# Schematic_v1_1.net
KiCad netlist of a schematic drawn in EasyEDA
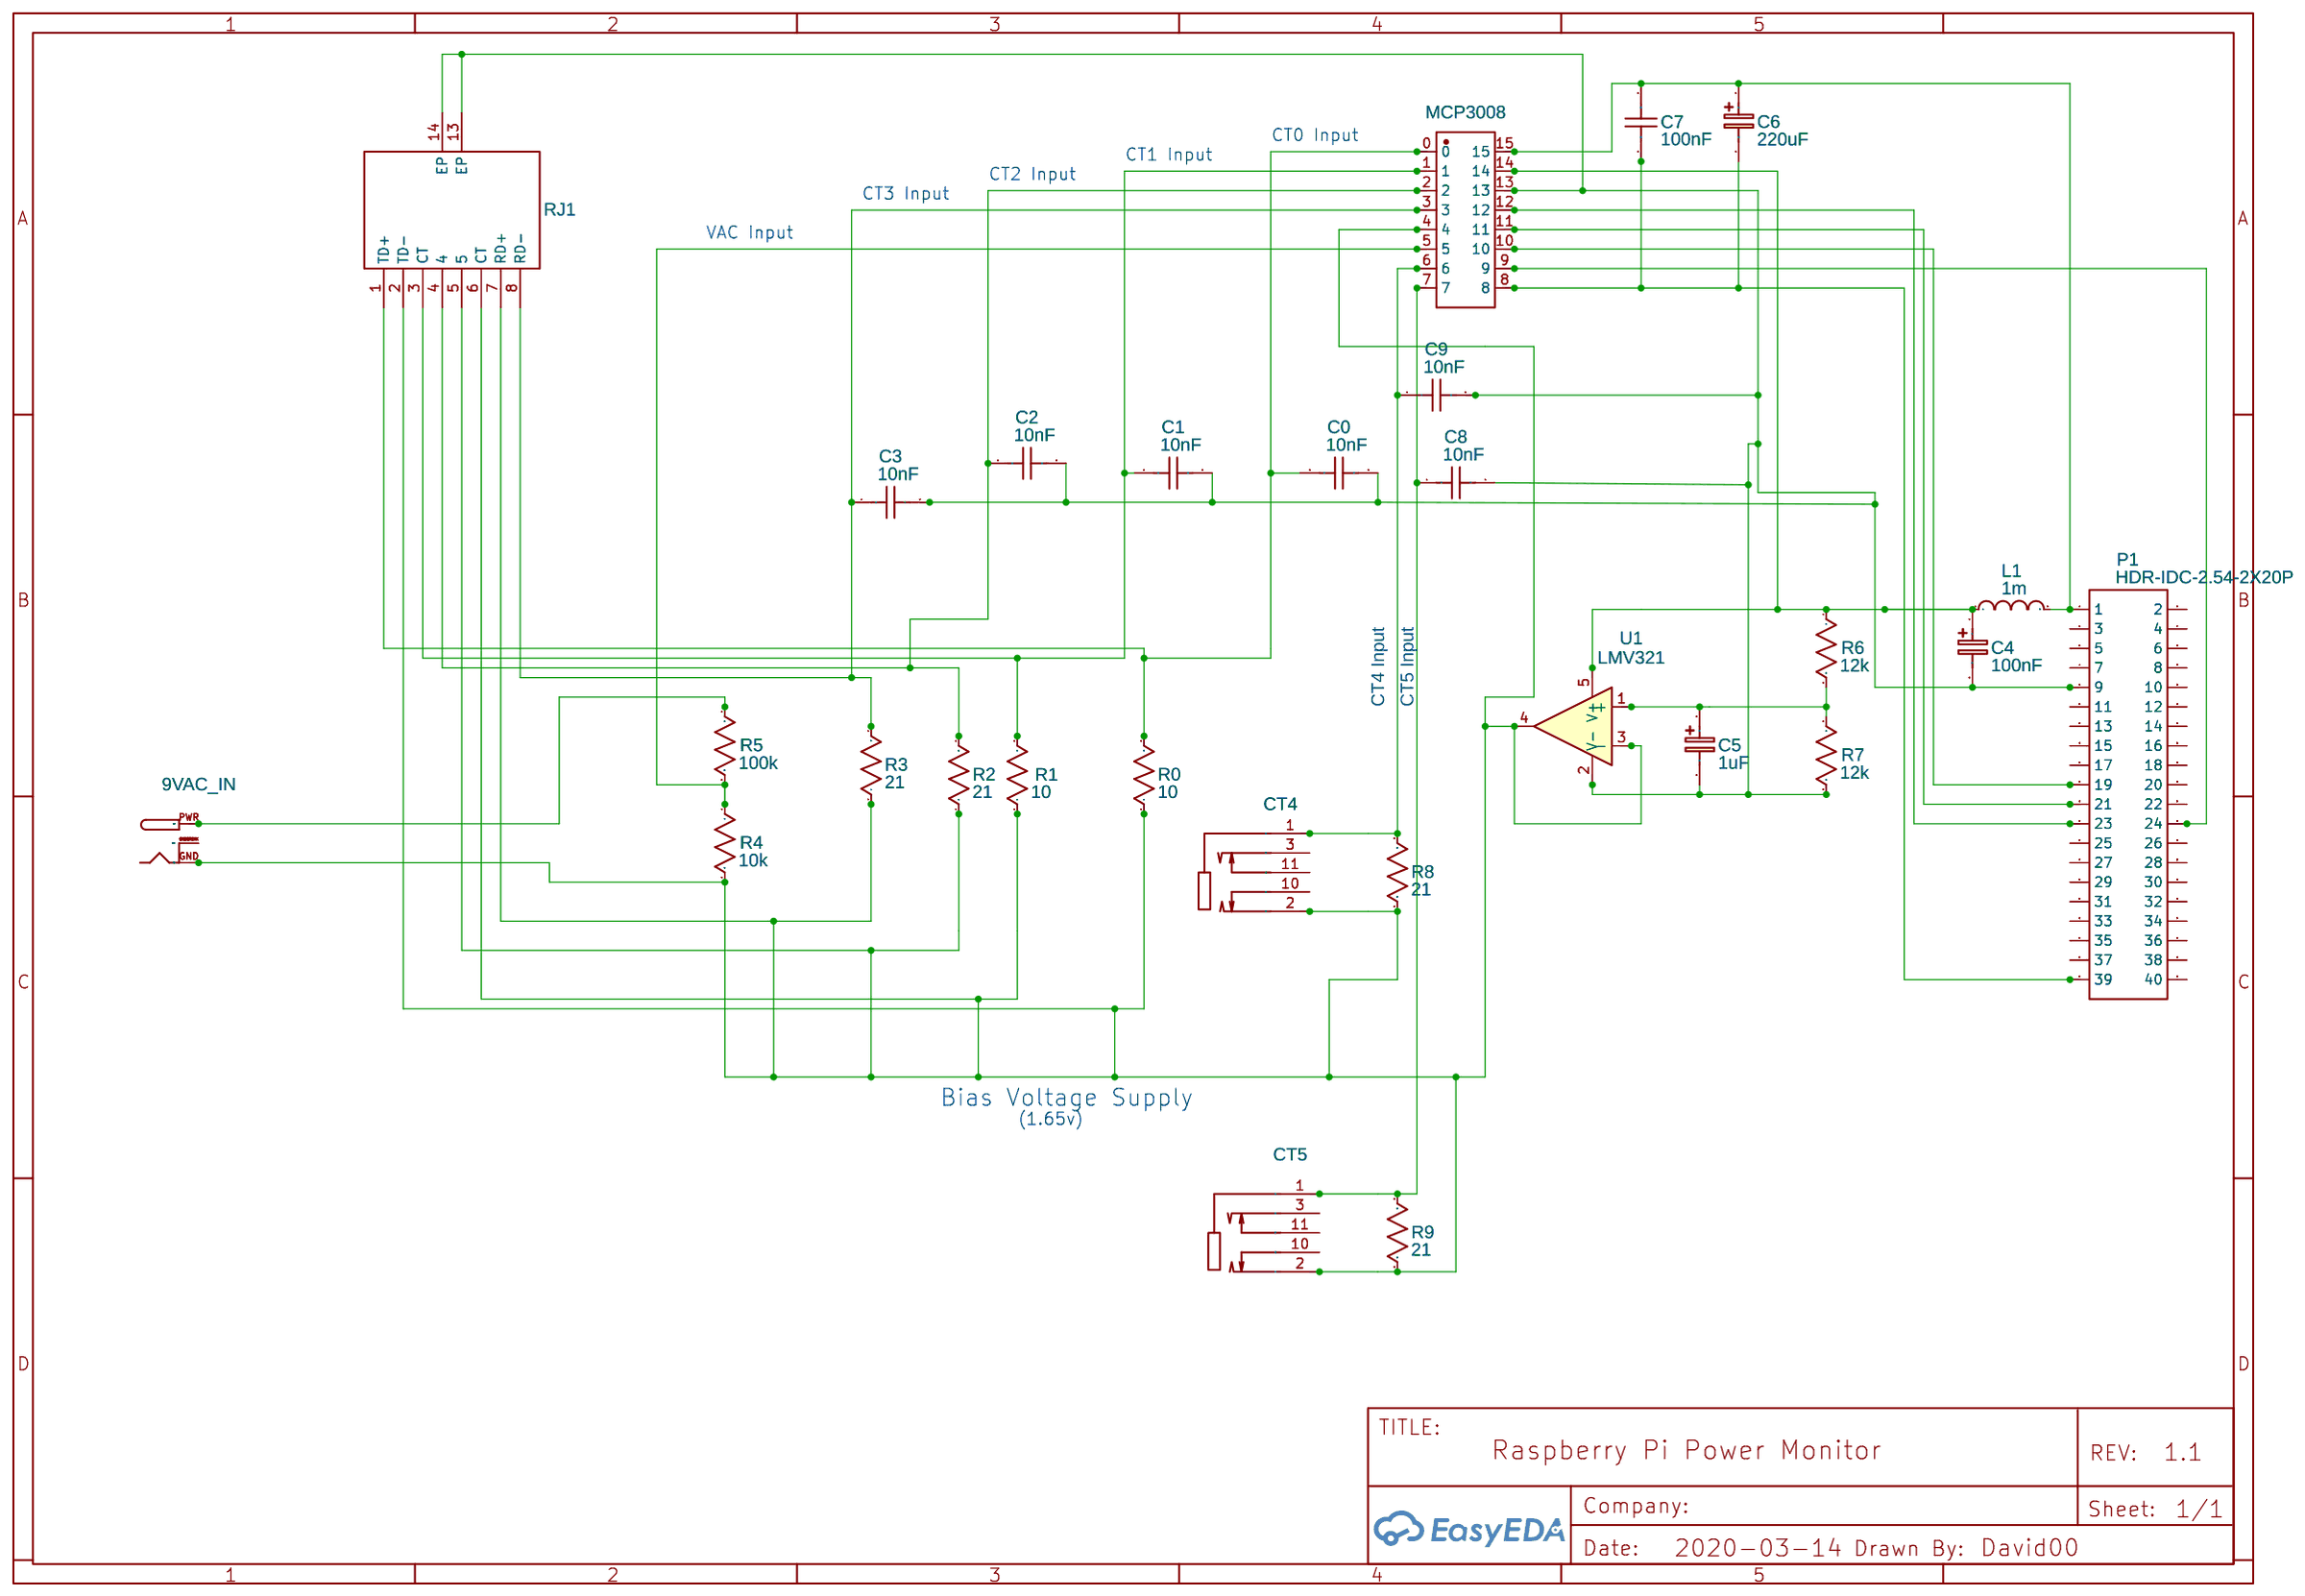
[diagram p0: schematic sheet]

(export (version "E")
  (design (tool "Eeschema 10.0.6"))
  (components
    (comp (ref "9VAC_IN") (value "DCBARRELPTH") (libsource (lib "") (part "DCBARRELPTH")))
    (comp (ref "C0")
      (value "10nF")
      (fields
        (field (name "BOM_Manufacturer Part") "PE103J2A0501")
        (field (name "BOM_Supplier Part") "C390168")
      )
      (libsource (lib "") (part "PE103J2A0501"))
    )
    (comp (ref "C1")
      (value "10nF")
      (fields
        (field (name "BOM_Manufacturer Part") "PE103J2A0501")
        (field (name "BOM_Supplier Part") "C390168")
      )
      (libsource (lib "") (part "PE103J2A0501"))
    )
    (comp (ref "C2")
      (value "10nF")
      (fields
        (field (name "BOM_Manufacturer Part") "PE103J2A0501")
        (field (name "BOM_Supplier Part") "C390168")
      )
      (libsource (lib "") (part "PE103J2A0501"))
    )
    (comp (ref "C3")
      (value "10nF")
      (fields
        (field (name "BOM_Manufacturer Part") "PE103J2A0501")
        (field (name "BOM_Supplier Part") "C390168")
      )
      (libsource (lib "") (part "PE103J2A0501"))
    )
    (comp (ref "C4") (value "100nF") (libsource (lib "") (part "Cap_Electrolytic(TH)_D3.0XF1.5_EU")))
    (comp (ref "C5") (value "1uF") (libsource (lib "") (part "Cap_Electrolytic(TH)_D3.0XF1.5_EU")))
    (comp (ref "C6") (value "220uF") (libsource (lib "") (part "Cap_Electrolytic(TH)_D3.0XF1.5_EU_1")))
    (comp (ref "C7")
      (value "100nF")
      (fields
        (field (name "BOM_Manufacturer Part") "CC45SL3AD101JYVNA")
        (field (name "BOM_Supplier Part") "C342396")
      )
      (libsource (lib "") (part "CC45SL3AD101JYVNA"))
    )
    (comp (ref "C8")
      (value "10nF")
      (fields
        (field (name "BOM_Manufacturer Part") "PE103J2A0501")
        (field (name "BOM_Supplier Part") "C390168")
      )
      (libsource (lib "") (part "PE103J2A0501"))
    )
    (comp (ref "C9")
      (value "10nF")
      (fields
        (field (name "BOM_Manufacturer Part") "PE103J2A0501")
        (field (name "BOM_Supplier Part") "C390168")
      )
      (libsource (lib "") (part "PE103J2A0501"))
    )
    (comp (ref "CT4")
      (value "PJ-328A0-B")
      (fields (field (name "BOM_Supplier Part") "C381129"))
      (libsource (lib "") (part "PJ-328A0-B"))
    )
    (comp (ref "CT5")
      (value "PJ-328A0-B")
      (fields (field (name "BOM_Supplier Part") "C381129"))
      (libsource (lib "") (part "PJ-328A0-B"))
    )
    (comp (ref "L1") (value "1m") (libsource (lib "") (part "Inductor_AXIAL-0.4_US")))
    (comp (ref "MCP3008")
      (value "IC seat 16P")
      (fields (field (name "BOM_Supplier Part") "C2326"))
      (libsource (lib "") (part "IC seat 16P"))
    )
    (comp (ref "P1")
      (value "HDR-IDC-2.54-2X20P")
      (fields
        (field (name "BOM_Manufacturer Part") "IDC Box 2X20 2.54MM")
        (field (name "BOM_Supplier Part") "C9138")
      )
      (libsource (lib "") (part "HDR-IDC-2.54-2X20P"))
    )
    (comp (ref "R0") (value "10") (libsource (lib "") (part "Res_AXIAL-0.3(1/8W)_US")))
    (comp (ref "R1") (value "10") (libsource (lib "") (part "Res_AXIAL-0.3(1/8W)_US")))
    (comp (ref "R2") (value "21") (libsource (lib "") (part "Res_AXIAL-0.3(1/8W)_US")))
    (comp (ref "R3") (value "21") (libsource (lib "") (part "Res_AXIAL-0.3(1/8W)_US")))
    (comp (ref "R4") (value "10k") (libsource (lib "") (part "Res_AXIAL-0.3(1/8W)_US_1")))
    (comp (ref "R5") (value "100k") (libsource (lib "") (part "Res_AXIAL-0.3(1/8W)_US_1")))
    (comp (ref "R6") (value "12k") (libsource (lib "") (part "Res_AXIAL-0.3(1/8W)_US_1")))
    (comp (ref "R7") (value "12k") (libsource (lib "") (part "Res_AXIAL-0.3(1/8W)_US_1")))
    (comp (ref "R8") (value "21") (libsource (lib "") (part "Res_AXIAL-0.3(1/8W)_US")))
    (comp (ref "R9") (value "21") (libsource (lib "") (part "Res_AXIAL-0.3(1/8W)_US")))
    (comp (ref "RJ1")
      (value "13F-62ANWA2NL")
      (fields (field (name "BOM_Supplier Part") "C179761"))
      (libsource (lib "") (part "13F-62ANWA2NL"))
    )
    (comp (ref "U1") (value "LMV321") (libsource (lib "") (part "LMV321")))
  )
  (nets
    (net (code "1") (name "Net-(9VAC_IN-PadPWR)") (class "Default")
      (node (ref "9VAC_IN") (pin "PWR") (pinfunction "PWR_PWR") (pintype "passive"))
      (node (ref "R5") (pin "1") (pinfunction "1_1") (pintype "unspecified"))
    )
    (net (code "2") (name "Net-(C1-Pad1)") (class "Default")
      (node (ref "C1") (pin "1") (pinfunction "1_1") (pintype "unspecified"))
      (node (ref "MCP3008") (pin "1") (pinfunction "1_1") (pintype "unspecified"))
      (node (ref "R1") (pin "2") (pinfunction "2_2") (pintype "unspecified"))
      (node (ref "RJ1") (pin "3") (pinfunction "CT_3") (pintype "unspecified"))
    )
    (net (code "3") (name "Net-(C2-Pad1)") (class "Default")
      (node (ref "C2") (pin "1") (pinfunction "1_1") (pintype "unspecified"))
      (node (ref "MCP3008") (pin "2") (pinfunction "2_2") (pintype "unspecified"))
      (node (ref "R2") (pin "2") (pinfunction "2_2") (pintype "unspecified"))
      (node (ref "RJ1") (pin "4") (pinfunction "4_4") (pintype "unspecified"))
    )
    (net (code "4") (name "Net-(C6-Pad1)") (class "Default")
      (node (ref "C6") (pin "1") (pinfunction "1_1") (pintype "unspecified"))
      (node (ref "C7") (pin "2") (pinfunction "2_2") (pintype "unspecified"))
      (node (ref "L1") (pin "2") (pinfunction "2_2") (pintype "unspecified"))
      (node (ref "MCP3008") (pin "15") (pinfunction "15_15") (pintype "unspecified"))
      (node (ref "P1") (pin "1") (pinfunction "1_1") (pintype "unspecified"))
    )
    (net (code "5") (name "Net-(C6-Pad2)") (class "Default")
      (node (ref "C6") (pin "2") (pinfunction "2_2") (pintype "unspecified"))
      (node (ref "C7") (pin "1") (pinfunction "1_1") (pintype "unspecified"))
      (node (ref "MCP3008") (pin "8") (pinfunction "8_8") (pintype "unspecified"))
      (node (ref "P1") (pin "39") (pinfunction "39_39") (pintype "unspecified"))
    )
    (net (code "6") (name "Net-(C8-Pad1)") (class "Default")
      (node (ref "C8") (pin "1") (pinfunction "1_1") (pintype "unspecified"))
      (node (ref "CT5") (pin "1") (pinfunction "1_1") (pintype "unspecified"))
      (node (ref "MCP3008") (pin "7") (pinfunction "7_7") (pintype "unspecified"))
      (node (ref "R9") (pin "2") (pinfunction "2_2") (pintype "unspecified"))
    )
    (net (code "7") (name "Net-(C9-Pad1)") (class "Default")
      (node (ref "C9") (pin "1") (pinfunction "1_1") (pintype "unspecified"))
      (node (ref "CT4") (pin "1") (pinfunction "1_1") (pintype "unspecified"))
      (node (ref "MCP3008") (pin "6") (pinfunction "6_6") (pintype "unspecified"))
      (node (ref "R8") (pin "2") (pinfunction "2_2") (pintype "unspecified"))
    )
    (net (code "8") (name "Net-(MCP3008-Pad5)") (class "Default")
      (node (ref "MCP3008") (pin "5") (pinfunction "5_5") (pintype "unspecified"))
      (node (ref "R4") (pin "1") (pinfunction "1_1") (pintype "unspecified"))
      (node (ref "R5") (pin "2") (pinfunction "2_2") (pintype "unspecified"))
    )
    (net (code "9") (name "Net-(MCP3008-Pad9)") (class "Default")
      (node (ref "MCP3008") (pin "9") (pinfunction "9_9") (pintype "unspecified"))
      (node (ref "P1") (pin "24") (pinfunction "24_24") (pintype "unspecified"))
    )
    (net (code "10") (name "Net-(MCP3008-Pad10)") (class "Default")
      (node (ref "MCP3008") (pin "10") (pinfunction "10_10") (pintype "unspecified"))
      (node (ref "P1") (pin "19") (pinfunction "19_19") (pintype "unspecified"))
    )
    (net (code "11") (name "Net-(MCP3008-Pad11)") (class "Default")
      (node (ref "MCP3008") (pin "11") (pinfunction "11_11") (pintype "unspecified"))
      (node (ref "P1") (pin "21") (pinfunction "21_21") (pintype "unspecified"))
    )
    (net (code "12") (name "Net-(MCP3008-Pad12)") (class "Default")
      (node (ref "MCP3008") (pin "12") (pinfunction "12_12") (pintype "unspecified"))
      (node (ref "P1") (pin "23") (pinfunction "23_23") (pintype "unspecified"))
    )
    (net (code "13") (name "Net-(RJ1-RD+)") (class "Default")
      (node (ref "9VAC_IN") (pin "GND") (pinfunction "GND_GND") (pintype "passive"))
      (node (ref "CT4") (pin "2") (pinfunction "2_2") (pintype "unspecified"))
      (node (ref "CT5") (pin "2") (pinfunction "2_2") (pintype "unspecified"))
      (node (ref "MCP3008") (pin "4") (pinfunction "4_4") (pintype "unspecified"))
      (node (ref "R0") (pin "1") (pinfunction "1_1") (pintype "unspecified"))
      (node (ref "R1") (pin "1") (pinfunction "1_1") (pintype "unspecified"))
      (node (ref "R2") (pin "1") (pinfunction "1_1") (pintype "unspecified"))
      (node (ref "R3") (pin "1") (pinfunction "1_1") (pintype "unspecified"))
      (node (ref "R4") (pin "2") (pinfunction "2_2") (pintype "unspecified"))
      (node (ref "R8") (pin "1") (pinfunction "1_1") (pintype "unspecified"))
      (node (ref "R9") (pin "1") (pinfunction "1_1") (pintype "unspecified"))
      (node (ref "RJ1") (pin "2") (pinfunction "TD-_2") (pintype "unspecified"))
      (node (ref "RJ1") (pin "5") (pinfunction "5_5") (pintype "unspecified"))
      (node (ref "RJ1") (pin "6") (pinfunction "CT_6") (pintype "unspecified"))
      (node (ref "RJ1") (pin "7") (pinfunction "RD+_7") (pintype "unspecified"))
      (node (ref "U1") (pin "3") (pinfunction "-_3") (pintype "input"))
      (node (ref "U1") (pin "4") (pintype "output"))
    )
    (net (code "14") (name "Net-(RJ1-RD-)") (class "Default")
      (node (ref "C3") (pin "1") (pinfunction "1_1") (pintype "unspecified"))
      (node (ref "MCP3008") (pin "3") (pinfunction "3_3") (pintype "unspecified"))
      (node (ref "R3") (pin "2") (pinfunction "2_2") (pintype "unspecified"))
      (node (ref "RJ1") (pin "8") (pinfunction "RD-_8") (pintype "unspecified"))
    )
    (net (code "15") (name "Net-(RJ1-TD+)") (class "Default")
      (node (ref "C0") (pin "1") (pinfunction "1_1") (pintype "unspecified"))
      (node (ref "MCP3008") (pin "0") (pinfunction "0_0") (pintype "unspecified"))
      (node (ref "R0") (pin "2") (pinfunction "2_2") (pintype "unspecified"))
      (node (ref "RJ1") (pin "1") (pinfunction "TD+_1") (pintype "unspecified"))
    )
    (net (code "16") (name "Net-(U1-+)") (class "Default")
      (node (ref "C5") (pin "1") (pinfunction "1_1") (pintype "unspecified"))
      (node (ref "R6") (pin "2") (pinfunction "2_2") (pintype "unspecified"))
      (node (ref "R7") (pin "1") (pinfunction "1_1") (pintype "unspecified"))
      (node (ref "U1") (pin "1") (pinfunction "+_1") (pintype "input"))
    )
    (net (code "17") (name "Net-(U1-V+)") (class "Default")
      (node (ref "C4") (pin "1") (pinfunction "1_1") (pintype "unspecified"))
      (node (ref "L1") (pin "1") (pinfunction "1_1") (pintype "unspecified"))
      (node (ref "MCP3008") (pin "14") (pinfunction "14_14") (pintype "unspecified"))
      (node (ref "R6") (pin "1") (pinfunction "1_1") (pintype "unspecified"))
      (node (ref "U1") (pin "5") (pinfunction "V+_5") (pintype "bidirectional"))
    )
    (net (code "18") (name "Net-(U1-V-)") (class "Default")
      (node (ref "C0") (pin "2") (pinfunction "2_2") (pintype "unspecified"))
      (node (ref "C1") (pin "2") (pinfunction "2_2") (pintype "unspecified"))
      (node (ref "C2") (pin "2") (pinfunction "2_2") (pintype "unspecified"))
      (node (ref "C3") (pin "2") (pinfunction "2_2") (pintype "unspecified"))
      (node (ref "C4") (pin "2") (pinfunction "2_2") (pintype "unspecified"))
      (node (ref "C5") (pin "2") (pinfunction "2_2") (pintype "unspecified"))
      (node (ref "C8") (pin "2") (pinfunction "2_2") (pintype "unspecified"))
      (node (ref "C9") (pin "2") (pinfunction "2_2") (pintype "unspecified"))
      (node (ref "MCP3008") (pin "13") (pinfunction "13_13") (pintype "unspecified"))
      (node (ref "P1") (pin "9") (pinfunction "9_9") (pintype "unspecified"))
      (node (ref "R7") (pin "2") (pinfunction "2_2") (pintype "unspecified"))
      (node (ref "RJ1") (pin "13") (pinfunction "EP_13") (pintype "unspecified"))
      (node (ref "RJ1") (pin "14") (pinfunction "EP_14") (pintype "unspecified"))
      (node (ref "U1") (pin "2") (pinfunction "V-_2") (pintype "bidirectional"))
    )
    (net (code "19") (name "unconnected-(9VAC_IN-PadGNDBREAK)") (class "Default")
      (node (ref "9VAC_IN") (pin "GNDBREAK") (pinfunction "GNDBREAK_GNDBREAK") (pintype "passive"))
    )
    (net (code "20") (name "unconnected-(CT4-Pad3)") (class "Default")
      (node (ref "CT4") (pin "3") (pinfunction "3_3") (pintype "unspecified"))
    )
    (net (code "21") (name "unconnected-(CT4-Pad10)") (class "Default")
      (node (ref "CT4") (pin "10") (pinfunction "10_10") (pintype "unspecified"))
    )
    (net (code "22") (name "unconnected-(CT4-Pad11)") (class "Default")
      (node (ref "CT4") (pin "11") (pinfunction "11_11") (pintype "unspecified"))
    )
    (net (code "23") (name "unconnected-(CT5-Pad3)") (class "Default")
      (node (ref "CT5") (pin "3") (pinfunction "3_3") (pintype "unspecified"))
    )
    (net (code "24") (name "unconnected-(CT5-Pad10)") (class "Default")
      (node (ref "CT5") (pin "10") (pinfunction "10_10") (pintype "unspecified"))
    )
    (net (code "25") (name "unconnected-(CT5-Pad11)") (class "Default")
      (node (ref "CT5") (pin "11") (pinfunction "11_11") (pintype "unspecified"))
    )
    (net (code "26") (name "unconnected-(P1-Pad2)") (class "Default")
      (node (ref "P1") (pin "2") (pinfunction "2_2") (pintype "unspecified"))
    )
    (net (code "27") (name "unconnected-(P1-Pad3)") (class "Default")
      (node (ref "P1") (pin "3") (pinfunction "3_3") (pintype "unspecified"))
    )
    (net (code "28") (name "unconnected-(P1-Pad4)") (class "Default")
      (node (ref "P1") (pin "4") (pinfunction "4_4") (pintype "unspecified"))
    )
    (net (code "29") (name "unconnected-(P1-Pad5)") (class "Default")
      (node (ref "P1") (pin "5") (pinfunction "5_5") (pintype "unspecified"))
    )
    (net (code "30") (name "unconnected-(P1-Pad6)") (class "Default")
      (node (ref "P1") (pin "6") (pinfunction "6_6") (pintype "unspecified"))
    )
    (net (code "31") (name "unconnected-(P1-Pad7)") (class "Default")
      (node (ref "P1") (pin "7") (pinfunction "7_7") (pintype "unspecified"))
    )
    (net (code "32") (name "unconnected-(P1-Pad8)") (class "Default")
      (node (ref "P1") (pin "8") (pinfunction "8_8") (pintype "unspecified"))
    )
    (net (code "33") (name "unconnected-(P1-Pad10)") (class "Default")
      (node (ref "P1") (pin "10") (pinfunction "10_10") (pintype "unspecified"))
    )
    (net (code "34") (name "unconnected-(P1-Pad11)") (class "Default")
      (node (ref "P1") (pin "11") (pinfunction "11_11") (pintype "unspecified"))
    )
    (net (code "35") (name "unconnected-(P1-Pad12)") (class "Default")
      (node (ref "P1") (pin "12") (pinfunction "12_12") (pintype "unspecified"))
    )
    (net (code "36") (name "unconnected-(P1-Pad13)") (class "Default")
      (node (ref "P1") (pin "13") (pinfunction "13_13") (pintype "unspecified"))
    )
    (net (code "37") (name "unconnected-(P1-Pad14)") (class "Default")
      (node (ref "P1") (pin "14") (pinfunction "14_14") (pintype "unspecified"))
    )
    (net (code "38") (name "unconnected-(P1-Pad15)") (class "Default")
      (node (ref "P1") (pin "15") (pinfunction "15_15") (pintype "unspecified"))
    )
    (net (code "39") (name "unconnected-(P1-Pad16)") (class "Default")
      (node (ref "P1") (pin "16") (pinfunction "16_16") (pintype "unspecified"))
    )
    (net (code "40") (name "unconnected-(P1-Pad17)") (class "Default")
      (node (ref "P1") (pin "17") (pinfunction "17_17") (pintype "unspecified"))
    )
    (net (code "41") (name "unconnected-(P1-Pad18)") (class "Default")
      (node (ref "P1") (pin "18") (pinfunction "18_18") (pintype "unspecified"))
    )
    (net (code "42") (name "unconnected-(P1-Pad20)") (class "Default")
      (node (ref "P1") (pin "20") (pinfunction "20_20") (pintype "unspecified"))
    )
    (net (code "43") (name "unconnected-(P1-Pad22)") (class "Default")
      (node (ref "P1") (pin "22") (pinfunction "22_22") (pintype "unspecified"))
    )
    (net (code "44") (name "unconnected-(P1-Pad25)") (class "Default")
      (node (ref "P1") (pin "25") (pinfunction "25_25") (pintype "unspecified"))
    )
    (net (code "45") (name "unconnected-(P1-Pad26)") (class "Default")
      (node (ref "P1") (pin "26") (pinfunction "26_26") (pintype "unspecified"))
    )
    (net (code "46") (name "unconnected-(P1-Pad27)") (class "Default")
      (node (ref "P1") (pin "27") (pinfunction "27_27") (pintype "unspecified"))
    )
    (net (code "47") (name "unconnected-(P1-Pad28)") (class "Default")
      (node (ref "P1") (pin "28") (pinfunction "28_28") (pintype "unspecified"))
    )
    (net (code "48") (name "unconnected-(P1-Pad29)") (class "Default")
      (node (ref "P1") (pin "29") (pinfunction "29_29") (pintype "unspecified"))
    )
    (net (code "49") (name "unconnected-(P1-Pad30)") (class "Default")
      (node (ref "P1") (pin "30") (pinfunction "30_30") (pintype "unspecified"))
    )
    (net (code "50") (name "unconnected-(P1-Pad31)") (class "Default")
      (node (ref "P1") (pin "31") (pinfunction "31_31") (pintype "unspecified"))
    )
    (net (code "51") (name "unconnected-(P1-Pad32)") (class "Default")
      (node (ref "P1") (pin "32") (pinfunction "32_32") (pintype "unspecified"))
    )
    (net (code "52") (name "unconnected-(P1-Pad33)") (class "Default")
      (node (ref "P1") (pin "33") (pinfunction "33_33") (pintype "unspecified"))
    )
    (net (code "53") (name "unconnected-(P1-Pad34)") (class "Default")
      (node (ref "P1") (pin "34") (pinfunction "34_34") (pintype "unspecified"))
    )
    (net (code "54") (name "unconnected-(P1-Pad35)") (class "Default")
      (node (ref "P1") (pin "35") (pinfunction "35_35") (pintype "unspecified"))
    )
    (net (code "55") (name "unconnected-(P1-Pad36)") (class "Default")
      (node (ref "P1") (pin "36") (pinfunction "36_36") (pintype "unspecified"))
    )
    (net (code "56") (name "unconnected-(P1-Pad37)") (class "Default")
      (node (ref "P1") (pin "37") (pinfunction "37_37") (pintype "unspecified"))
    )
    (net (code "57") (name "unconnected-(P1-Pad38)") (class "Default")
      (node (ref "P1") (pin "38") (pinfunction "38_38") (pintype "unspecified"))
    )
    (net (code "58") (name "unconnected-(P1-Pad40)") (class "Default")
      (node (ref "P1") (pin "40") (pinfunction "40_40") (pintype "unspecified"))
    )
  )
)
